# optical_pickup.net
KiCad netlist of a schematic drawn in EasyEDA
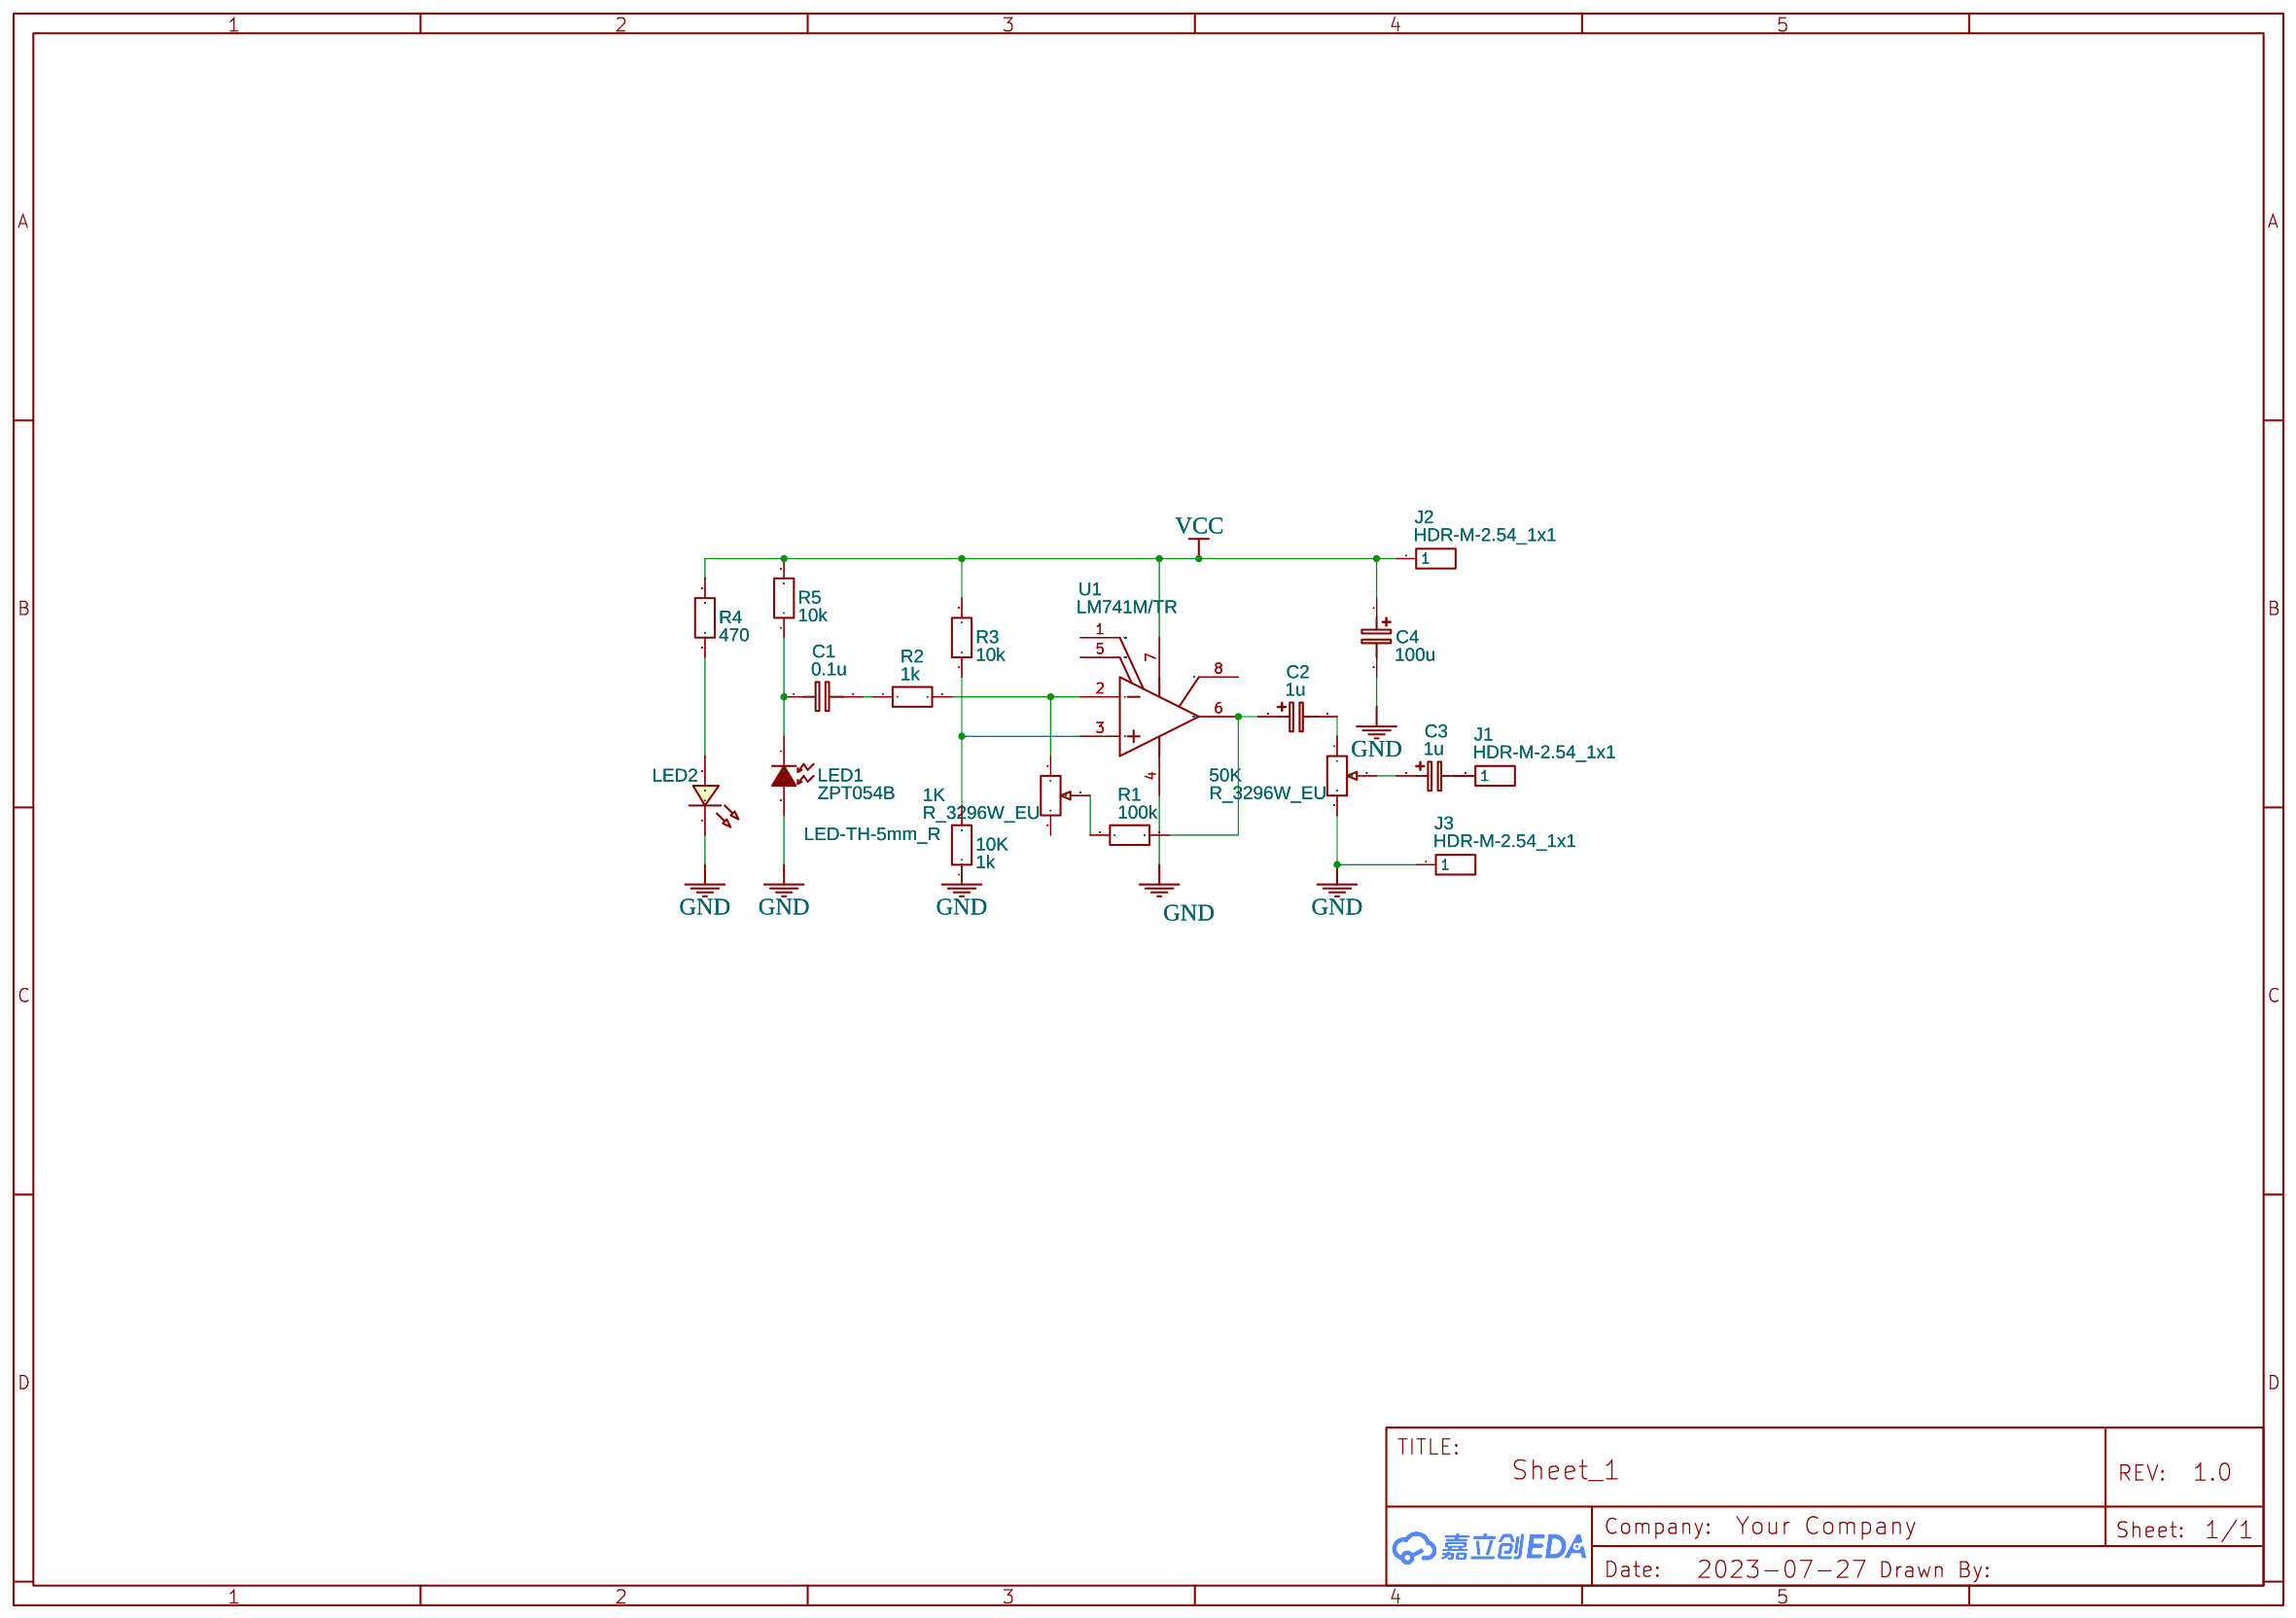
[diagram p0: schematic sheet]

(export (version "E")
  (design (tool "Eeschema 10.0.6"))
  (components
    (comp (ref "1K") (value "R_3296W_EU") (libsource (lib "") (part "R_3296W_EU_1")))
    (comp (ref "10K") (value "1k") (libsource (lib "") (part "R_0603_EU_1")))
    (comp (ref "50K") (value "R_3296W_EU") (libsource (lib "") (part "R_3296W_EU")))
    (comp (ref "C1") (value "0.1u") (libsource (lib "") (part "C_0603_EU")))
    (comp (ref "C2") (value "1u") (libsource (lib "") (part "C_Tan_SMD_A_EU")))
    (comp (ref "C3") (value "1u") (libsource (lib "") (part "C_Tan_SMD_A_EU")))
    (comp (ref "C4") (value "100u") (libsource (lib "") (part "C_Tan_SMD_A_EU_1")))
    (comp (ref "J1")
      (value "HDR-M-2.54_1x1")
      (fields (field (name "BOM_Supplier Part") "C81276"))
      (libsource (lib "") (part "HDR-M-2.54_1x1"))
    )
    (comp (ref "J2")
      (value "HDR-M-2.54_1x1")
      (fields (field (name "BOM_Supplier Part") "C81276"))
      (libsource (lib "") (part "HDR-M-2.54_1x1"))
    )
    (comp (ref "J3")
      (value "HDR-M-2.54_1x1")
      (fields (field (name "BOM_Supplier Part") "C81276"))
      (libsource (lib "") (part "HDR-M-2.54_1x1"))
    )
    (comp (ref "LED1")
      (value "ZPT054B")
      (fields (field (name "Manufacturer") "Chau Light"))
      (libsource (lib "") (part "ZPT054B"))
    )
    (comp (ref "LED2")
      (value "LED-TH-5mm_R")
      (fields
        (field (name "BOM_Manufacturer Part") "333-2SURD/S530-A3")
        (field (name "BOM_Supplier Part") "C87271")
      )
      (libsource (lib "") (part "LED-TH-5mm_R"))
    )
    (comp (ref "R1") (value "100k") (libsource (lib "") (part "R_0603_EU")))
    (comp (ref "R2") (value "1k") (libsource (lib "") (part "R_0603_EU")))
    (comp (ref "R3") (value "10k") (libsource (lib "") (part "R_0603_EU_2")))
    (comp (ref "R4") (value "470") (libsource (lib "") (part "R_0603_EU_2")))
    (comp (ref "R5") (value "10k") (libsource (lib "") (part "R_0603_EU_2")))
    (comp (ref "U1")
      (value "LM741M/TR")
      (fields (field (name "Manufacturer") "HGSEMI(华冠)"))
      (libsource (lib "") (part "LM741M/TR"))
    )
  )
  (nets
    (net (code "1") (name "GND") (class "Default")
      (node (ref "10K") (pin "1") (pinfunction "1_1") (pintype "unspecified"))
      (node (ref "50K") (pin "3") (pinfunction "3_3") (pintype "input"))
      (node (ref "C4") (pin "2") (pinfunction "2_2") (pintype "unspecified"))
      (node (ref "J3") (pin "1") (pinfunction "1_1") (pintype "input"))
      (node (ref "LED1") (pin "2") (pinfunction "C_2") (pintype "input"))
      (node (ref "LED2") (pin "2") (pinfunction "2_2") (pintype "unspecified"))
      (node (ref "U1") (pin "4") (pinfunction "V-_4") (pintype "passive"))
    )
    (net (code "2") (name "Net-(1K-Pad2)") (class "Default")
      (node (ref "1K") (pin "2") (pinfunction "2_2") (pintype "input"))
      (node (ref "R1") (pin "1") (pinfunction "1_1") (pintype "unspecified"))
    )
    (net (code "3") (name "Net-(50K-Pad1)") (class "Default")
      (node (ref "50K") (pin "1") (pinfunction "1_1") (pintype "input"))
      (node (ref "C2") (pin "2") (pinfunction "2_2") (pintype "unspecified"))
    )
    (net (code "4") (name "Net-(50K-Pad2)") (class "Default")
      (node (ref "50K") (pin "2") (pinfunction "2_2") (pintype "input"))
      (node (ref "C3") (pin "1") (pinfunction "1_1") (pintype "unspecified"))
    )
    (net (code "5") (name "Net-(C1-Pad2)") (class "Default")
      (node (ref "C1") (pin "2") (pinfunction "2_2") (pintype "unspecified"))
      (node (ref "R2") (pin "1") (pinfunction "1_1") (pintype "unspecified"))
    )
    (net (code "6") (name "Net-(C3-Pad2)") (class "Default")
      (node (ref "C3") (pin "2") (pinfunction "2_2") (pintype "unspecified"))
      (node (ref "J1") (pin "1") (pinfunction "1_1") (pintype "input"))
    )
    (net (code "7") (name "Net-(LED1-E)") (class "Default")
      (node (ref "C1") (pin "1") (pinfunction "1_1") (pintype "unspecified"))
      (node (ref "LED1") (pin "1") (pinfunction "E_1") (pintype "input"))
      (node (ref "R5") (pin "1") (pinfunction "1_1") (pintype "unspecified"))
    )
    (net (code "8") (name "Net-(LED2-Pad1)") (class "Default")
      (node (ref "LED2") (pin "1") (pinfunction "1_1") (pintype "unspecified"))
      (node (ref "R4") (pin "1") (pinfunction "1_1") (pintype "unspecified"))
    )
    (net (code "9") (name "Net-(U1-IN+)") (class "Default")
      (node (ref "10K") (pin "2") (pinfunction "2_2") (pintype "unspecified"))
      (node (ref "R3") (pin "1") (pinfunction "1_1") (pintype "unspecified"))
      (node (ref "U1") (pin "3") (pinfunction "IN+_3") (pintype "unspecified"))
    )
    (net (code "10") (name "Net-(U1-IN-)") (class "Default")
      (node (ref "1K") (pin "1") (pinfunction "1_1") (pintype "input"))
      (node (ref "R2") (pin "2") (pinfunction "2_2") (pintype "unspecified"))
      (node (ref "U1") (pin "2") (pinfunction "IN-_2") (pintype "unspecified"))
    )
    (net (code "11") (name "Net-(U1-OUT)") (class "Default")
      (node (ref "C2") (pin "1") (pinfunction "1_1") (pintype "unspecified"))
      (node (ref "R1") (pin "2") (pinfunction "2_2") (pintype "unspecified"))
      (node (ref "U1") (pin "6") (pinfunction "OUT_6") (pintype "output"))
    )
    (net (code "12") (name "VCC") (class "Default")
      (node (ref "C4") (pin "1") (pinfunction "1_1") (pintype "unspecified"))
      (node (ref "J2") (pin "1") (pinfunction "1_1") (pintype "input"))
      (node (ref "R3") (pin "2") (pinfunction "2_2") (pintype "unspecified"))
      (node (ref "R4") (pin "2") (pinfunction "2_2") (pintype "unspecified"))
      (node (ref "R5") (pin "2") (pinfunction "2_2") (pintype "unspecified"))
      (node (ref "U1") (pin "7") (pinfunction "V+_7") (pintype "passive"))
    )
    (net (code "13") (name "unconnected-(1K-Pad3)") (class "Default")
      (node (ref "1K") (pin "3") (pinfunction "3_3") (pintype "input"))
    )
    (net (code "14") (name "unconnected-(U1-NC-Pad8)") (class "Default")
      (node (ref "U1") (pin "8") (pinfunction "NC_8") (pintype "unspecified"))
    )
    (net (code "15") (name "unconnected-(U1-OFFSET_NULL-Pad1)") (class "Default")
      (node (ref "U1") (pin "1") (pinfunction "OFFSET_NULL_1") (pintype "unspecified"))
    )
    (net (code "16") (name "unconnected-(U1-OFFSET_NULL-Pad5)") (class "Default")
      (node (ref "U1") (pin "5") (pinfunction "OFFSET_NULL_5") (pintype "unspecified"))
    )
  )
)
